# untitled.net
KiCad netlist of a schematic drawn in EAGLE
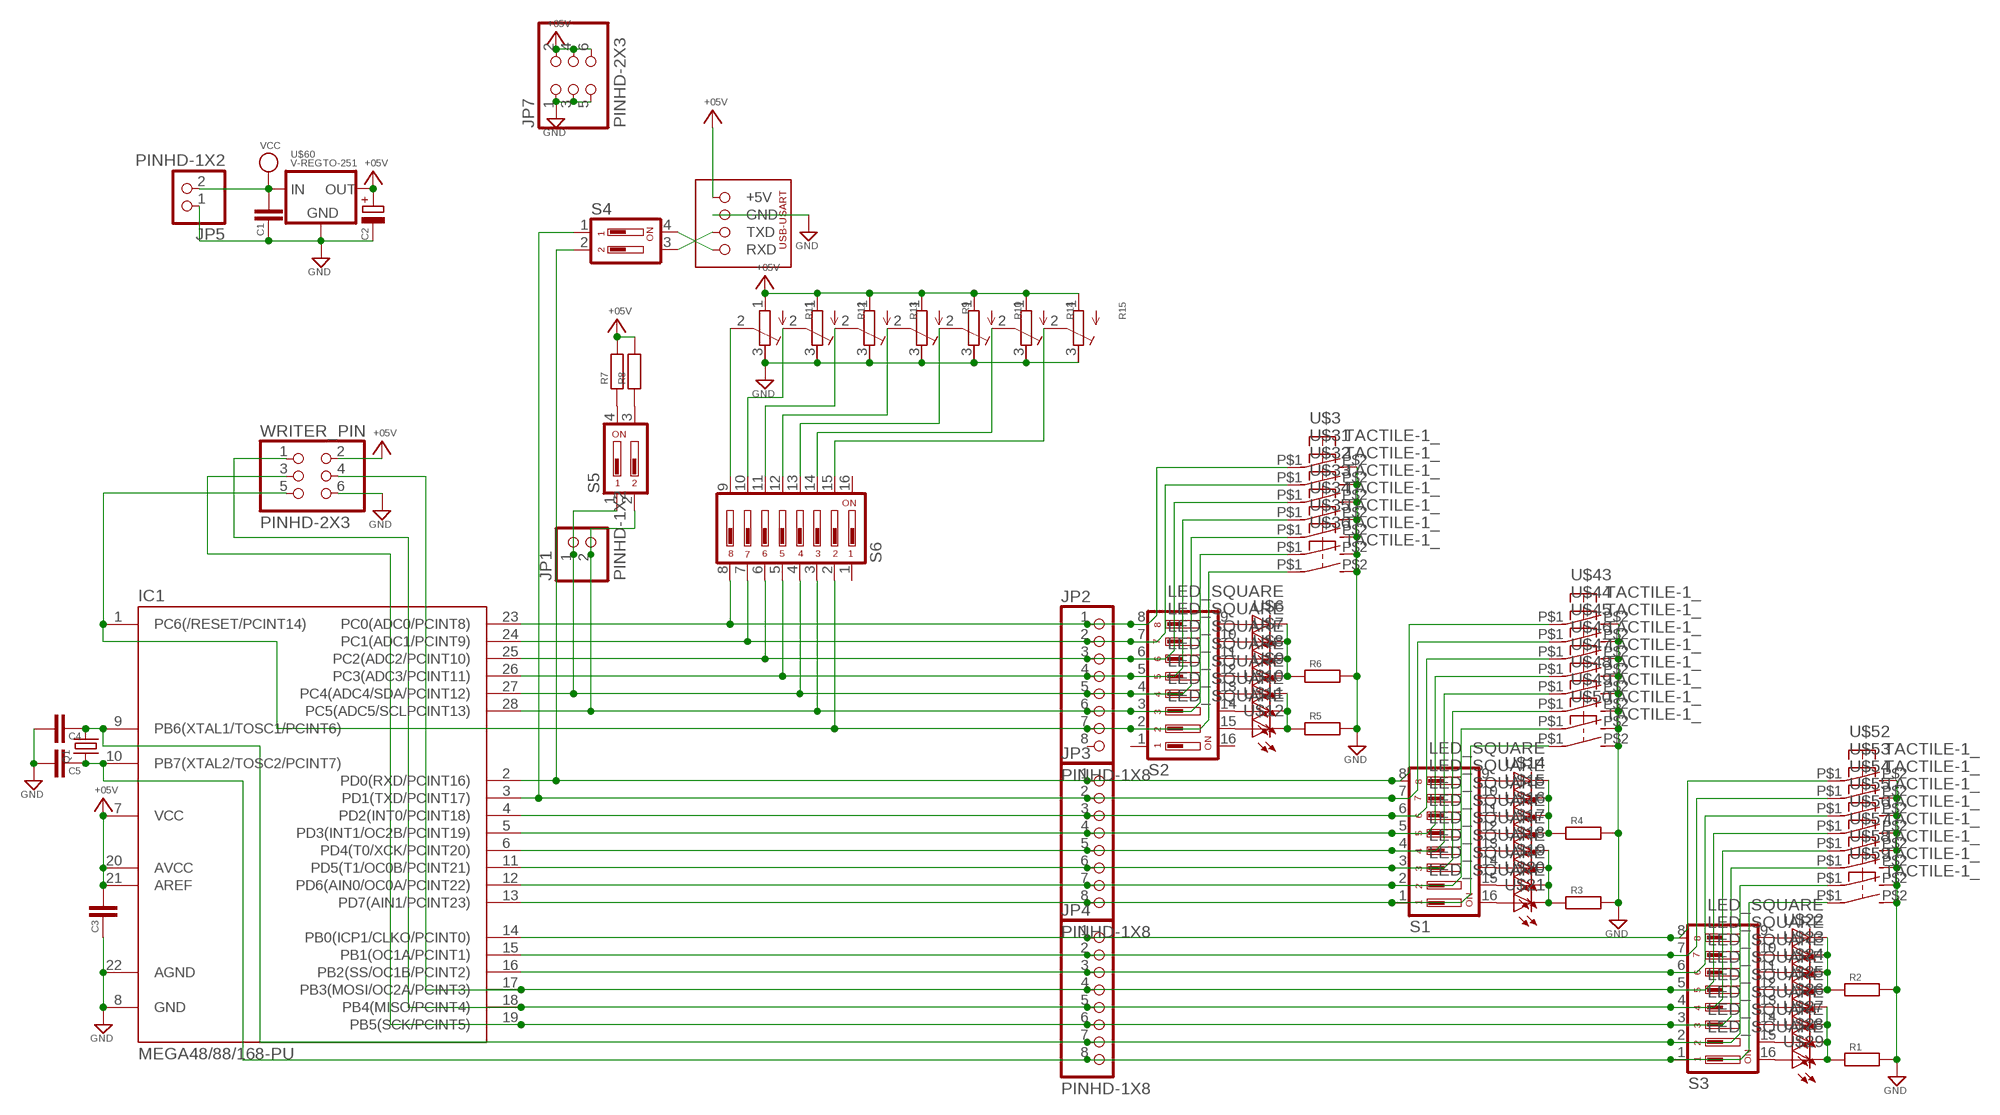
[diagram p0: schematic, sheet 1]

(export (version "E")
  (design (tool "Eeschema 10.0.6"))
  (components
    (comp (ref "C1")
      (value "C-025-025X050")
      (footprint "eagle-import:C025-025X050")
      (libsource (lib "eagle-import") (part "C-025-025X050"))
    )
    (comp (ref "C2")
      (value "CPOL-E2.5-6")
      (footprint "eagle-import:E2,5-6")
      (libsource (lib "eagle-import") (part "CPOL-E2.5-6"))
    )
    (comp (ref "C3")
      (value "C-025-025X050")
      (footprint "eagle-import:C025-025X050")
      (libsource (lib "eagle-import") (part "C-025-025X050"))
    )
    (comp (ref "C4")
      (value "C-025-025X050")
      (footprint "eagle-import:C025-025X050")
      (libsource (lib "eagle-import") (part "C-025-025X050"))
    )
    (comp (ref "C5")
      (value "C-025-025X050")
      (footprint "eagle-import:C025-025X050")
      (libsource (lib "eagle-import") (part "C-025-025X050"))
    )
    (comp (ref "IC1")
      (value "MEGA48/88/168-PU")
      (footprint "eagle-import:DIL28-3")
      (libsource (lib "eagle-import") (part "MEGA48/88/168-PU"))
    )
    (comp (ref "JP1")
      (value "PINHD-1X2")
      (footprint "eagle-import:1X02")
      (libsource (lib "eagle-import") (part "PINHD-1X2"))
    )
    (comp (ref "JP2")
      (value "PINHD-1X8")
      (footprint "eagle-import:1X08")
      (libsource (lib "eagle-import") (part "PINHD-1X8"))
    )
    (comp (ref "JP3")
      (value "PINHD-1X8")
      (footprint "eagle-import:1X08")
      (libsource (lib "eagle-import") (part "PINHD-1X8"))
    )
    (comp (ref "JP4")
      (value "PINHD-1X8")
      (footprint "eagle-import:1X08")
      (libsource (lib "eagle-import") (part "PINHD-1X8"))
    )
    (comp (ref "JP5")
      (value "PINHD-1X2")
      (footprint "eagle-import:1X02")
      (libsource (lib "eagle-import") (part "PINHD-1X2"))
    )
    (comp (ref "JP7")
      (value "PINHD-2X3")
      (footprint "eagle-import:2X03")
      (libsource (lib "eagle-import") (part "PINHD-2X3"))
    )
    (comp (ref "Q1")
      (value "CRYSTALHC49S")
      (footprint "eagle-import:HC49_S")
      (libsource (lib "eagle-import") (part "CRYSTALHC49S"))
    )
    (comp (ref "R1")
      (value "R-EU_1/4W(8MM)")
      (footprint "eagle-import:1_4W(8MM)")
      (libsource (lib "eagle-import") (part "R-EU_1/4W(8MM)"))
    )
    (comp (ref "R2")
      (value "R-EU_1/4W(8MM)")
      (footprint "eagle-import:1_4W(8MM)")
      (libsource (lib "eagle-import") (part "R-EU_1/4W(8MM)"))
    )
    (comp (ref "R3")
      (value "R-EU_1/4W(8MM)")
      (footprint "eagle-import:1_4W(8MM)")
      (libsource (lib "eagle-import") (part "R-EU_1/4W(8MM)"))
    )
    (comp (ref "R4")
      (value "R-EU_1/4W(8MM)")
      (footprint "eagle-import:1_4W(8MM)")
      (libsource (lib "eagle-import") (part "R-EU_1/4W(8MM)"))
    )
    (comp (ref "R5")
      (value "R-EU_1/4W(8MM)")
      (footprint "eagle-import:1_4W(8MM)")
      (libsource (lib "eagle-import") (part "R-EU_1/4W(8MM)"))
    )
    (comp (ref "R6")
      (value "R-EU_1/4W(8MM)")
      (footprint "eagle-import:1_4W(8MM)")
      (libsource (lib "eagle-import") (part "R-EU_1/4W(8MM)"))
    )
    (comp (ref "R7")
      (value "R-EU_1/4W(8MM)")
      (footprint "eagle-import:1_4W(8MM)")
      (libsource (lib "eagle-import") (part "R-EU_1/4W(8MM)"))
    )
    (comp (ref "R8")
      (value "R-EU_1/4W(8MM)")
      (footprint "eagle-import:1_4W(8MM)")
      (libsource (lib "eagle-import") (part "R-EU_1/4W(8MM)"))
    )
    (comp (ref "R9")
      (value "R-TRIMM_3339P")
      (footprint "eagle-import:3339P")
      (libsource (lib "eagle-import") (part "R-TRIMM_3339P"))
    )
    (comp (ref "R10")
      (value "R-TRIMM_3339P")
      (footprint "eagle-import:3339P")
      (libsource (lib "eagle-import") (part "R-TRIMM_3339P"))
    )
    (comp (ref "R11")
      (value "R-TRIMM_3339P")
      (footprint "eagle-import:3339P")
      (libsource (lib "eagle-import") (part "R-TRIMM_3339P"))
    )
    (comp (ref "R12")
      (value "R-TRIMM_3339P")
      (footprint "eagle-import:3339P")
      (libsource (lib "eagle-import") (part "R-TRIMM_3339P"))
    )
    (comp (ref "R13")
      (value "R-TRIMM_3339P")
      (footprint "eagle-import:3339P")
      (libsource (lib "eagle-import") (part "R-TRIMM_3339P"))
    )
    (comp (ref "R14")
      (value "R-TRIMM_3339P")
      (footprint "eagle-import:3339P")
      (libsource (lib "eagle-import") (part "R-TRIMM_3339P"))
    )
    (comp (ref "R15")
      (value "R-TRIMM_3339P")
      (footprint "eagle-import:3339P")
      (libsource (lib "eagle-import") (part "R-TRIMM_3339P"))
    )
    (comp (ref "S1")
      (value "DIP08YL")
      (footprint "eagle-import:DIP08YL")
      (libsource (lib "eagle-import") (part "DIP08YL"))
    )
    (comp (ref "S2")
      (value "DIP08YL")
      (footprint "eagle-import:DIP08YL")
      (libsource (lib "eagle-import") (part "DIP08YL"))
    )
    (comp (ref "S3")
      (value "DIP08YL")
      (footprint "eagle-import:DIP08YL")
      (libsource (lib "eagle-import") (part "DIP08YL"))
    )
    (comp (ref "S4")
      (value "DIP02YL")
      (footprint "eagle-import:DIP02YL")
      (libsource (lib "eagle-import") (part "DIP02YL"))
    )
    (comp (ref "S5")
      (value "DIP02YL")
      (footprint "eagle-import:DIP02YL")
      (libsource (lib "eagle-import") (part "DIP02YL"))
    )
    (comp (ref "S6")
      (value "DIP08YL")
      (footprint "eagle-import:DIP08YL")
      (libsource (lib "eagle-import") (part "DIP08YL"))
    )
    (comp (ref "U$3")
      (value "TACTILE-1_")
      (footprint "eagle-import:TACTILE_")
      (libsource (lib "eagle-import") (part "TACTILE-1_"))
    )
    (comp (ref "U$6")
      (value "LED_SQUARE")
      (footprint "eagle-import:5020")
      (libsource (lib "eagle-import") (part "LED_SQUARE"))
    )
    (comp (ref "U$7")
      (value "LED_SQUARE")
      (footprint "eagle-import:5020")
      (libsource (lib "eagle-import") (part "LED_SQUARE"))
    )
    (comp (ref "U$8")
      (value "LED_SQUARE")
      (footprint "eagle-import:5020")
      (libsource (lib "eagle-import") (part "LED_SQUARE"))
    )
    (comp (ref "U$9")
      (value "LED_SQUARE")
      (footprint "eagle-import:5020")
      (libsource (lib "eagle-import") (part "LED_SQUARE"))
    )
    (comp (ref "U$10")
      (value "LED_SQUARE")
      (footprint "eagle-import:5020")
      (libsource (lib "eagle-import") (part "LED_SQUARE"))
    )
    (comp (ref "U$11")
      (value "LED_SQUARE")
      (footprint "eagle-import:5020")
      (libsource (lib "eagle-import") (part "LED_SQUARE"))
    )
    (comp (ref "U$12")
      (value "LED_SQUARE")
      (footprint "eagle-import:5020")
      (libsource (lib "eagle-import") (part "LED_SQUARE"))
    )
    (comp (ref "U$14")
      (value "LED_SQUARE")
      (footprint "eagle-import:5020")
      (libsource (lib "eagle-import") (part "LED_SQUARE"))
    )
    (comp (ref "U$15")
      (value "LED_SQUARE")
      (footprint "eagle-import:5020")
      (libsource (lib "eagle-import") (part "LED_SQUARE"))
    )
    (comp (ref "U$16")
      (value "LED_SQUARE")
      (footprint "eagle-import:5020")
      (libsource (lib "eagle-import") (part "LED_SQUARE"))
    )
    (comp (ref "U$17")
      (value "LED_SQUARE")
      (footprint "eagle-import:5020")
      (libsource (lib "eagle-import") (part "LED_SQUARE"))
    )
    (comp (ref "U$18")
      (value "LED_SQUARE")
      (footprint "eagle-import:5020")
      (libsource (lib "eagle-import") (part "LED_SQUARE"))
    )
    (comp (ref "U$19")
      (value "LED_SQUARE")
      (footprint "eagle-import:5020")
      (libsource (lib "eagle-import") (part "LED_SQUARE"))
    )
    (comp (ref "U$20")
      (value "LED_SQUARE")
      (footprint "eagle-import:5020")
      (libsource (lib "eagle-import") (part "LED_SQUARE"))
    )
    (comp (ref "U$21")
      (value "LED_SQUARE")
      (footprint "eagle-import:5020")
      (libsource (lib "eagle-import") (part "LED_SQUARE"))
    )
    (comp (ref "U$22")
      (value "LED_SQUARE")
      (footprint "eagle-import:5020")
      (libsource (lib "eagle-import") (part "LED_SQUARE"))
    )
    (comp (ref "U$23")
      (value "LED_SQUARE")
      (footprint "eagle-import:5020")
      (libsource (lib "eagle-import") (part "LED_SQUARE"))
    )
    (comp (ref "U$24")
      (value "LED_SQUARE")
      (footprint "eagle-import:5020")
      (libsource (lib "eagle-import") (part "LED_SQUARE"))
    )
    (comp (ref "U$25")
      (value "LED_SQUARE")
      (footprint "eagle-import:5020")
      (libsource (lib "eagle-import") (part "LED_SQUARE"))
    )
    (comp (ref "U$26")
      (value "LED_SQUARE")
      (footprint "eagle-import:5020")
      (libsource (lib "eagle-import") (part "LED_SQUARE"))
    )
    (comp (ref "U$27")
      (value "LED_SQUARE")
      (footprint "eagle-import:5020")
      (libsource (lib "eagle-import") (part "LED_SQUARE"))
    )
    (comp (ref "U$28")
      (value "LED_SQUARE")
      (footprint "eagle-import:5020")
      (libsource (lib "eagle-import") (part "LED_SQUARE"))
    )
    (comp (ref "U$29")
      (value "LED_SQUARE")
      (footprint "eagle-import:5020")
      (libsource (lib "eagle-import") (part "LED_SQUARE"))
    )
    (comp (ref "U$31")
      (value "TACTILE-1_")
      (footprint "eagle-import:TACTILE_")
      (libsource (lib "eagle-import") (part "TACTILE-1_"))
    )
    (comp (ref "U$32")
      (value "TACTILE-1_")
      (footprint "eagle-import:TACTILE_")
      (libsource (lib "eagle-import") (part "TACTILE-1_"))
    )
    (comp (ref "U$33")
      (value "TACTILE-1_")
      (footprint "eagle-import:TACTILE_")
      (libsource (lib "eagle-import") (part "TACTILE-1_"))
    )
    (comp (ref "U$34")
      (value "TACTILE-1_")
      (footprint "eagle-import:TACTILE_")
      (libsource (lib "eagle-import") (part "TACTILE-1_"))
    )
    (comp (ref "U$35")
      (value "TACTILE-1_")
      (footprint "eagle-import:TACTILE_")
      (libsource (lib "eagle-import") (part "TACTILE-1_"))
    )
    (comp (ref "U$36")
      (value "TACTILE-1_")
      (footprint "eagle-import:TACTILE_")
      (libsource (lib "eagle-import") (part "TACTILE-1_"))
    )
    (comp (ref "U$43")
      (value "TACTILE-1_")
      (footprint "eagle-import:TACTILE_")
      (libsource (lib "eagle-import") (part "TACTILE-1_"))
    )
    (comp (ref "U$44")
      (value "TACTILE-1_")
      (footprint "eagle-import:TACTILE_")
      (libsource (lib "eagle-import") (part "TACTILE-1_"))
    )
    (comp (ref "U$45")
      (value "TACTILE-1_")
      (footprint "eagle-import:TACTILE_")
      (libsource (lib "eagle-import") (part "TACTILE-1_"))
    )
    (comp (ref "U$46")
      (value "TACTILE-1_")
      (footprint "eagle-import:TACTILE_")
      (libsource (lib "eagle-import") (part "TACTILE-1_"))
    )
    (comp (ref "U$47")
      (value "TACTILE-1_")
      (footprint "eagle-import:TACTILE_")
      (libsource (lib "eagle-import") (part "TACTILE-1_"))
    )
    (comp (ref "U$48")
      (value "TACTILE-1_")
      (footprint "eagle-import:TACTILE_")
      (libsource (lib "eagle-import") (part "TACTILE-1_"))
    )
    (comp (ref "U$49")
      (value "TACTILE-1_")
      (footprint "eagle-import:TACTILE_")
      (libsource (lib "eagle-import") (part "TACTILE-1_"))
    )
    (comp (ref "U$50")
      (value "TACTILE-1_")
      (footprint "eagle-import:TACTILE_")
      (libsource (lib "eagle-import") (part "TACTILE-1_"))
    )
    (comp (ref "U$52")
      (value "TACTILE-1_")
      (footprint "eagle-import:TACTILE_")
      (libsource (lib "eagle-import") (part "TACTILE-1_"))
    )
    (comp (ref "U$53")
      (value "TACTILE-1_")
      (footprint "eagle-import:TACTILE_")
      (libsource (lib "eagle-import") (part "TACTILE-1_"))
    )
    (comp (ref "U$54")
      (value "TACTILE-1_")
      (footprint "eagle-import:TACTILE_")
      (libsource (lib "eagle-import") (part "TACTILE-1_"))
    )
    (comp (ref "U$55")
      (value "TACTILE-1_")
      (footprint "eagle-import:TACTILE_")
      (libsource (lib "eagle-import") (part "TACTILE-1_"))
    )
    (comp (ref "U$56")
      (value "TACTILE-1_")
      (footprint "eagle-import:TACTILE_")
      (libsource (lib "eagle-import") (part "TACTILE-1_"))
    )
    (comp (ref "U$57")
      (value "TACTILE-1_")
      (footprint "eagle-import:TACTILE_")
      (libsource (lib "eagle-import") (part "TACTILE-1_"))
    )
    (comp (ref "U$58")
      (value "TACTILE-1_")
      (footprint "eagle-import:TACTILE_")
      (libsource (lib "eagle-import") (part "TACTILE-1_"))
    )
    (comp (ref "U$59")
      (value "TACTILE-1_")
      (footprint "eagle-import:TACTILE_")
      (libsource (lib "eagle-import") (part "TACTILE-1_"))
    )
    (comp (ref "U$60")
      (value "V-REGTO-251")
      (footprint "eagle-import:TO-251")
      (libsource (lib "eagle-import") (part "V-REGTO-251"))
    )
    (comp (ref "U$64")
      (value "AE-FT234X")
      (footprint "eagle-import:AE-FT234X")
      (libsource (lib "eagle-import") (part "AE-FT234X"))
    )
    (comp (ref "WRITER_PIN")
      (value "PINHD-2X3")
      (footprint "eagle-import:2X03")
      (libsource (lib "eagle-import") (part "PINHD-2X3"))
    )
  )
  (nets
    (net (code "1") (name "+05V") (class "Default")
      (node (ref "C2") (pin "+") (pinfunction "+_+") (pintype "passive"))
      (node (ref "C3") (pin "1") (pinfunction "1_1") (pintype "passive"))
      (node (ref "IC1") (pin "20") (pinfunction "AVCC_20") (pintype "passive"))
      (node (ref "IC1") (pin "21") (pinfunction "AREF_21") (pintype "passive"))
      (node (ref "IC1") (pin "7") (pinfunction "VCC_7") (pintype "power_in"))
      (node (ref "JP7") (pin "2") (pinfunction "2_2") (pintype "passive"))
      (node (ref "JP7") (pin "4") (pinfunction "4_4") (pintype "passive"))
      (node (ref "JP7") (pin "6") (pinfunction "6_6") (pintype "passive"))
      (node (ref "R10") (pin "1") (pinfunction "E_1") (pintype "passive"))
      (node (ref "R11") (pin "1") (pinfunction "E_1") (pintype "passive"))
      (node (ref "R12") (pin "1") (pinfunction "E_1") (pintype "passive"))
      (node (ref "R13") (pin "1") (pinfunction "E_1") (pintype "passive"))
      (node (ref "R14") (pin "1") (pinfunction "E_1") (pintype "passive"))
      (node (ref "R15") (pin "1") (pinfunction "E_1") (pintype "passive"))
      (node (ref "R7") (pin "2") (pinfunction "2_2") (pintype "passive"))
      (node (ref "R8") (pin "2") (pinfunction "2_2") (pintype "passive"))
      (node (ref "R9") (pin "1") (pinfunction "E_1") (pintype "passive"))
      (node (ref "U$60") (pin "3") (pinfunction "OUT_3") (pintype "passive"))
      (node (ref "U$64") (pin "P$1") (pinfunction "+5V_P$1") (pintype "bidirectional"))
      (node (ref "WRITER_PIN") (pin "2") (pinfunction "2_2") (pintype "passive"))
    )
    (net (code "2") (name "GND") (class "Default")
      (node (ref "C1") (pin "2") (pinfunction "2_2") (pintype "passive"))
      (node (ref "C2") (pin "-") (pinfunction "-_-") (pintype "passive"))
      (node (ref "C3") (pin "2") (pinfunction "2_2") (pintype "passive"))
      (node (ref "C4") (pin "1") (pinfunction "1_1") (pintype "passive"))
      (node (ref "C5") (pin "1") (pinfunction "1_1") (pintype "passive"))
      (node (ref "IC1") (pin "22") (pinfunction "AGND_22") (pintype "power_in"))
      (node (ref "IC1") (pin "8") (pinfunction "GND_8") (pintype "power_in"))
      (node (ref "JP5") (pin "1") (pinfunction "1_1") (pintype "passive"))
      (node (ref "JP7") (pin "1") (pinfunction "1_1") (pintype "passive"))
      (node (ref "JP7") (pin "3") (pinfunction "3_3") (pintype "passive"))
      (node (ref "JP7") (pin "5") (pinfunction "5_5") (pintype "passive"))
      (node (ref "R1") (pin "2") (pinfunction "2_2") (pintype "passive"))
      (node (ref "R10") (pin "3") (pinfunction "A_3") (pintype "passive"))
      (node (ref "R11") (pin "3") (pinfunction "A_3") (pintype "passive"))
      (node (ref "R12") (pin "3") (pinfunction "A_3") (pintype "passive"))
      (node (ref "R13") (pin "3") (pinfunction "A_3") (pintype "passive"))
      (node (ref "R14") (pin "3") (pinfunction "A_3") (pintype "passive"))
      (node (ref "R15") (pin "3") (pinfunction "A_3") (pintype "passive"))
      (node (ref "R2") (pin "2") (pinfunction "2_2") (pintype "passive"))
      (node (ref "R3") (pin "2") (pinfunction "2_2") (pintype "passive"))
      (node (ref "R4") (pin "2") (pinfunction "2_2") (pintype "passive"))
      (node (ref "R5") (pin "2") (pinfunction "2_2") (pintype "passive"))
      (node (ref "R6") (pin "2") (pinfunction "2_2") (pintype "passive"))
      (node (ref "R9") (pin "3") (pinfunction "A_3") (pintype "passive"))
      (node (ref "U$3") (pin "P$2") (pinfunction "S_P$2") (pintype "passive"))
      (node (ref "U$31") (pin "P$2") (pinfunction "S_P$2") (pintype "passive"))
      (node (ref "U$32") (pin "P$2") (pinfunction "S_P$2") (pintype "passive"))
      (node (ref "U$33") (pin "P$2") (pinfunction "S_P$2") (pintype "passive"))
      (node (ref "U$34") (pin "P$2") (pinfunction "S_P$2") (pintype "passive"))
      (node (ref "U$35") (pin "P$2") (pinfunction "S_P$2") (pintype "passive"))
      (node (ref "U$36") (pin "P$2") (pinfunction "S_P$2") (pintype "passive"))
      (node (ref "U$43") (pin "P$2") (pinfunction "S_P$2") (pintype "passive"))
      (node (ref "U$44") (pin "P$2") (pinfunction "S_P$2") (pintype "passive"))
      (node (ref "U$45") (pin "P$2") (pinfunction "S_P$2") (pintype "passive"))
      (node (ref "U$46") (pin "P$2") (pinfunction "S_P$2") (pintype "passive"))
      (node (ref "U$47") (pin "P$2") (pinfunction "S_P$2") (pintype "passive"))
      (node (ref "U$48") (pin "P$2") (pinfunction "S_P$2") (pintype "passive"))
      (node (ref "U$49") (pin "P$2") (pinfunction "S_P$2") (pintype "passive"))
      (node (ref "U$50") (pin "P$2") (pinfunction "S_P$2") (pintype "passive"))
      (node (ref "U$52") (pin "P$2") (pinfunction "S_P$2") (pintype "passive"))
      (node (ref "U$53") (pin "P$2") (pinfunction "S_P$2") (pintype "passive"))
      (node (ref "U$54") (pin "P$2") (pinfunction "S_P$2") (pintype "passive"))
      (node (ref "U$55") (pin "P$2") (pinfunction "S_P$2") (pintype "passive"))
      (node (ref "U$56") (pin "P$2") (pinfunction "S_P$2") (pintype "passive"))
      (node (ref "U$57") (pin "P$2") (pinfunction "S_P$2") (pintype "passive"))
      (node (ref "U$58") (pin "P$2") (pinfunction "S_P$2") (pintype "passive"))
      (node (ref "U$59") (pin "P$2") (pinfunction "S_P$2") (pintype "passive"))
      (node (ref "U$60") (pin "2") (pinfunction "GND_2") (pintype "input"))
      (node (ref "U$64") (pin "P$2") (pinfunction "GND_P$2") (pintype "bidirectional"))
      (node (ref "WRITER_PIN") (pin "6") (pinfunction "6_6") (pintype "passive"))
    )
    (net (code "3") (name "Net-(IC1-PB0(ICP1{slash}CLKO{slash}PCINT0))") (class "Default")
      (node (ref "IC1") (pin "14") (pinfunction "PB0(ICP1/CLKO/PCINT0)_14") (pintype "bidirectional"))
      (node (ref "JP4") (pin "1") (pinfunction "1_1") (pintype "passive"))
      (node (ref "S3") (pin "8") (pinfunction "8_8") (pintype "passive"))
      (node (ref "U$52") (pin "P$1") (pinfunction "P_P$1") (pintype "passive"))
    )
    (net (code "4") (name "Net-(IC1-PB1(OC1A{slash}PCINT1))") (class "Default")
      (node (ref "IC1") (pin "15") (pinfunction "PB1(OC1A/PCINT1)_15") (pintype "bidirectional"))
      (node (ref "JP4") (pin "2") (pinfunction "2_2") (pintype "passive"))
      (node (ref "S3") (pin "7") (pinfunction "7_7") (pintype "passive"))
      (node (ref "U$53") (pin "P$1") (pinfunction "P_P$1") (pintype "passive"))
    )
    (net (code "5") (name "Net-(IC1-PB2(SS{slash}OC1B{slash}PCINT2))") (class "Default")
      (node (ref "IC1") (pin "16") (pinfunction "PB2(SS/OC1B/PCINT2)_16") (pintype "bidirectional"))
      (node (ref "JP4") (pin "3") (pinfunction "3_3") (pintype "passive"))
      (node (ref "S3") (pin "6") (pinfunction "6_6") (pintype "passive"))
      (node (ref "U$54") (pin "P$1") (pinfunction "P_P$1") (pintype "passive"))
    )
    (net (code "6") (name "Net-(IC1-PB3(MOSI{slash}OC2A{slash}PCINT3))") (class "Default")
      (node (ref "IC1") (pin "17") (pinfunction "PB3(MOSI/OC2A/PCINT3)_17") (pintype "bidirectional"))
      (node (ref "JP4") (pin "4") (pinfunction "4_4") (pintype "passive"))
      (node (ref "S3") (pin "5") (pinfunction "5_5") (pintype "passive"))
      (node (ref "U$55") (pin "P$1") (pinfunction "P_P$1") (pintype "passive"))
      (node (ref "WRITER_PIN") (pin "4") (pinfunction "4_4") (pintype "passive"))
    )
    (net (code "7") (name "Net-(IC1-PB4(MISO{slash}PCINT4))") (class "Default")
      (node (ref "IC1") (pin "18") (pinfunction "PB4(MISO/PCINT4)_18") (pintype "bidirectional"))
      (node (ref "JP4") (pin "5") (pinfunction "5_5") (pintype "passive"))
      (node (ref "S3") (pin "4") (pinfunction "4_4") (pintype "passive"))
      (node (ref "U$56") (pin "P$1") (pinfunction "P_P$1") (pintype "passive"))
      (node (ref "WRITER_PIN") (pin "1") (pinfunction "1_1") (pintype "passive"))
    )
    (net (code "8") (name "Net-(IC1-PB5(SCK{slash}PCINT5))") (class "Default")
      (node (ref "IC1") (pin "19") (pinfunction "PB5(SCK/PCINT5)_19") (pintype "bidirectional"))
      (node (ref "JP4") (pin "6") (pinfunction "6_6") (pintype "passive"))
      (node (ref "S3") (pin "3") (pinfunction "3_3") (pintype "passive"))
      (node (ref "U$57") (pin "P$1") (pinfunction "P_P$1") (pintype "passive"))
      (node (ref "WRITER_PIN") (pin "3") (pinfunction "3_3") (pintype "passive"))
    )
    (net (code "9") (name "Net-(IC1-PB6(XTAL1{slash}TOSC1{slash}PCINT6))") (class "Default")
      (node (ref "C4") (pin "2") (pinfunction "2_2") (pintype "passive"))
      (node (ref "IC1") (pin "9") (pinfunction "PB6(XTAL1/TOSC1/PCINT6)_9") (pintype "bidirectional"))
      (node (ref "JP4") (pin "7") (pinfunction "7_7") (pintype "passive"))
      (node (ref "Q1") (pin "2") (pinfunction "2_2") (pintype "passive"))
      (node (ref "S3") (pin "2") (pinfunction "2_2") (pintype "passive"))
      (node (ref "U$58") (pin "P$1") (pinfunction "P_P$1") (pintype "passive"))
    )
    (net (code "10") (name "Net-(IC1-PB7(XTAL2{slash}TOSC2{slash}PCINT7))") (class "Default")
      (node (ref "C5") (pin "2") (pinfunction "2_2") (pintype "passive"))
      (node (ref "IC1") (pin "10") (pinfunction "PB7(XTAL2/TOSC2/PCINT7)_10") (pintype "bidirectional"))
      (node (ref "JP4") (pin "8") (pinfunction "8_8") (pintype "passive"))
      (node (ref "Q1") (pin "1") (pinfunction "1_1") (pintype "passive"))
      (node (ref "S3") (pin "1") (pinfunction "1_1") (pintype "passive"))
      (node (ref "U$59") (pin "P$1") (pinfunction "P_P$1") (pintype "passive"))
    )
    (net (code "11") (name "Net-(IC1-PC0(ADC0{slash}PCINT8))") (class "Default")
      (node (ref "IC1") (pin "23") (pinfunction "PC0(ADC0/PCINT8)_23") (pintype "bidirectional"))
      (node (ref "JP2") (pin "1") (pinfunction "1_1") (pintype "passive"))
      (node (ref "S2") (pin "8") (pinfunction "8_8") (pintype "passive"))
      (node (ref "S6") (pin "8") (pinfunction "8_8") (pintype "passive"))
      (node (ref "U$3") (pin "P$1") (pinfunction "P_P$1") (pintype "passive"))
    )
    (net (code "12") (name "Net-(IC1-PC1(ADC1{slash}PCINT9))") (class "Default")
      (node (ref "IC1") (pin "24") (pinfunction "PC1(ADC1/PCINT9)_24") (pintype "bidirectional"))
      (node (ref "JP2") (pin "2") (pinfunction "2_2") (pintype "passive"))
      (node (ref "S2") (pin "7") (pinfunction "7_7") (pintype "passive"))
      (node (ref "S6") (pin "7") (pinfunction "7_7") (pintype "passive"))
      (node (ref "U$31") (pin "P$1") (pinfunction "P_P$1") (pintype "passive"))
    )
    (net (code "13") (name "Net-(IC1-PC2(ADC2{slash}PCINT10))") (class "Default")
      (node (ref "IC1") (pin "25") (pinfunction "PC2(ADC2/PCINT10)_25") (pintype "bidirectional"))
      (node (ref "JP2") (pin "3") (pinfunction "3_3") (pintype "passive"))
      (node (ref "S2") (pin "6") (pinfunction "6_6") (pintype "passive"))
      (node (ref "S6") (pin "6") (pinfunction "6_6") (pintype "passive"))
      (node (ref "U$32") (pin "P$1") (pinfunction "P_P$1") (pintype "passive"))
    )
    (net (code "14") (name "Net-(IC1-PC3(ADC3{slash}PCINT11))") (class "Default")
      (node (ref "IC1") (pin "26") (pinfunction "PC3(ADC3/PCINT11)_26") (pintype "bidirectional"))
      (node (ref "JP2") (pin "4") (pinfunction "4_4") (pintype "passive"))
      (node (ref "S2") (pin "5") (pinfunction "5_5") (pintype "passive"))
      (node (ref "S6") (pin "5") (pinfunction "5_5") (pintype "passive"))
      (node (ref "U$33") (pin "P$1") (pinfunction "P_P$1") (pintype "passive"))
    )
    (net (code "15") (name "Net-(IC1-PC4(ADC4{slash}SDA{slash}PCINT12))") (class "Default")
      (node (ref "IC1") (pin "27") (pinfunction "PC4(ADC4/SDA/PCINT12)_27") (pintype "bidirectional"))
      (node (ref "JP1") (pin "1") (pinfunction "1_1") (pintype "passive"))
      (node (ref "JP2") (pin "5") (pinfunction "5_5") (pintype "passive"))
      (node (ref "S2") (pin "4") (pinfunction "4_4") (pintype "passive"))
      (node (ref "S5") (pin "1") (pinfunction "1_1") (pintype "passive"))
      (node (ref "S6") (pin "4") (pinfunction "4_4") (pintype "passive"))
      (node (ref "U$34") (pin "P$1") (pinfunction "P_P$1") (pintype "passive"))
    )
    (net (code "16") (name "Net-(IC1-PC5(ADC5{slash}SCLPCINT13))") (class "Default")
      (node (ref "IC1") (pin "28") (pinfunction "PC5(ADC5/SCLPCINT13)_28") (pintype "bidirectional"))
      (node (ref "JP1") (pin "2") (pinfunction "2_2") (pintype "passive"))
      (node (ref "JP2") (pin "6") (pinfunction "6_6") (pintype "passive"))
      (node (ref "S2") (pin "3") (pinfunction "3_3") (pintype "passive"))
      (node (ref "S5") (pin "2") (pinfunction "2_2") (pintype "passive"))
      (node (ref "S6") (pin "3") (pinfunction "3_3") (pintype "passive"))
      (node (ref "U$35") (pin "P$1") (pinfunction "P_P$1") (pintype "passive"))
    )
    (net (code "17") (name "Net-(IC1-PC6({slash}RESET{slash}PCINT14))") (class "Default")
      (node (ref "IC1") (pin "1") (pinfunction "PC6(/RESET/PCINT14)_1") (pintype "bidirectional"))
      (node (ref "JP2") (pin "7") (pinfunction "7_7") (pintype "passive"))
      (node (ref "S2") (pin "2") (pinfunction "2_2") (pintype "passive"))
      (node (ref "S6") (pin "2") (pinfunction "2_2") (pintype "passive"))
      (node (ref "U$36") (pin "P$1") (pinfunction "P_P$1") (pintype "passive"))
      (node (ref "WRITER_PIN") (pin "5") (pinfunction "5_5") (pintype "passive"))
    )
    (net (code "18") (name "Net-(IC1-PD0(RXD{slash}PCINT16))") (class "Default")
      (node (ref "IC1") (pin "2") (pinfunction "PD0(RXD/PCINT16)_2") (pintype "bidirectional"))
      (node (ref "JP3") (pin "1") (pinfunction "1_1") (pintype "passive"))
      (node (ref "S1") (pin "8") (pinfunction "8_8") (pintype "passive"))
      (node (ref "S4") (pin "2") (pinfunction "2_2") (pintype "passive"))
      (node (ref "U$43") (pin "P$1") (pinfunction "P_P$1") (pintype "passive"))
    )
    (net (code "19") (name "Net-(IC1-PD1(TXD{slash}PCINT17))") (class "Default")
      (node (ref "IC1") (pin "3") (pinfunction "PD1(TXD/PCINT17)_3") (pintype "bidirectional"))
      (node (ref "JP3") (pin "2") (pinfunction "2_2") (pintype "passive"))
      (node (ref "S1") (pin "7") (pinfunction "7_7") (pintype "passive"))
      (node (ref "S4") (pin "1") (pinfunction "1_1") (pintype "passive"))
      (node (ref "U$44") (pin "P$1") (pinfunction "P_P$1") (pintype "passive"))
    )
    (net (code "20") (name "Net-(IC1-PD2(INT0{slash}PCINT18))") (class "Default")
      (node (ref "IC1") (pin "4") (pinfunction "PD2(INT0/PCINT18)_4") (pintype "bidirectional"))
      (node (ref "JP3") (pin "3") (pinfunction "3_3") (pintype "passive"))
      (node (ref "S1") (pin "6") (pinfunction "6_6") (pintype "passive"))
      (node (ref "U$45") (pin "P$1") (pinfunction "P_P$1") (pintype "passive"))
    )
    (net (code "21") (name "Net-(IC1-PD3(INT1{slash}OC2B{slash}PCINT19))") (class "Default")
      (node (ref "IC1") (pin "5") (pinfunction "PD3(INT1/OC2B/PCINT19)_5") (pintype "bidirectional"))
      (node (ref "JP3") (pin "4") (pinfunction "4_4") (pintype "passive"))
      (node (ref "S1") (pin "5") (pinfunction "5_5") (pintype "passive"))
      (node (ref "U$46") (pin "P$1") (pinfunction "P_P$1") (pintype "passive"))
    )
    (net (code "22") (name "Net-(IC1-PD4(T0{slash}XCK{slash}PCINT20))") (class "Default")
      (node (ref "IC1") (pin "6") (pinfunction "PD4(T0/XCK/PCINT20)_6") (pintype "bidirectional"))
      (node (ref "JP3") (pin "5") (pinfunction "5_5") (pintype "passive"))
      (node (ref "S1") (pin "4") (pinfunction "4_4") (pintype "passive"))
      (node (ref "U$47") (pin "P$1") (pinfunction "P_P$1") (pintype "passive"))
    )
    (net (code "23") (name "Net-(IC1-PD5(T1{slash}OC0B{slash}PCINT21))") (class "Default")
      (node (ref "IC1") (pin "11") (pinfunction "PD5(T1/OC0B/PCINT21)_11") (pintype "bidirectional"))
      (node (ref "JP3") (pin "6") (pinfunction "6_6") (pintype "passive"))
      (node (ref "S1") (pin "3") (pinfunction "3_3") (pintype "passive"))
      (node (ref "U$48") (pin "P$1") (pinfunction "P_P$1") (pintype "passive"))
    )
    (net (code "24") (name "Net-(IC1-PD6(AIN0{slash}OC0A{slash}PCINT22))") (class "Default")
      (node (ref "IC1") (pin "12") (pinfunction "PD6(AIN0/OC0A/PCINT22)_12") (pintype "bidirectional"))
      (node (ref "JP3") (pin "7") (pinfunction "7_7") (pintype "passive"))
      (node (ref "S1") (pin "2") (pinfunction "2_2") (pintype "passive"))
      (node (ref "U$49") (pin "P$1") (pinfunction "P_P$1") (pintype "passive"))
    )
    (net (code "25") (name "Net-(IC1-PD7(AIN1{slash}PCINT23))") (class "Default")
      (node (ref "IC1") (pin "13") (pinfunction "PD7(AIN1/PCINT23)_13") (pintype "bidirectional"))
      (node (ref "JP3") (pin "8") (pinfunction "8_8") (pintype "passive"))
      (node (ref "S1") (pin "1") (pinfunction "1_1") (pintype "passive"))
      (node (ref "U$50") (pin "P$1") (pinfunction "P_P$1") (pintype "passive"))
    )
    (net (code "26") (name "Net-(R7-Pad1)") (class "Default")
      (node (ref "R7") (pin "1") (pinfunction "1_1") (pintype "passive"))
      (node (ref "S5") (pin "4") (pinfunction "4_4") (pintype "passive"))
    )
    (net (code "27") (name "Net-(R8-Pad1)") (class "Default")
      (node (ref "R8") (pin "1") (pinfunction "1_1") (pintype "passive"))
      (node (ref "S5") (pin "3") (pinfunction "3_3") (pintype "passive"))
    )
    (net (code "28") (name "Net-(R9-S)") (class "Default")
      (node (ref "R9") (pin "2") (pinfunction "S_2") (pintype "passive"))
      (node (ref "S6") (pin "12") (pinfunction "12_12") (pintype "passive"))
    )
    (net (code "29") (name "Net-(R10-S)") (class "Default")
      (node (ref "R10") (pin "2") (pinfunction "S_2") (pintype "passive"))
      (node (ref "S6") (pin "13") (pinfunction "13_13") (pintype "passive"))
    )
    (net (code "30") (name "Net-(R11-S)") (class "Default")
      (node (ref "R11") (pin "2") (pinfunction "S_2") (pintype "passive"))
      (node (ref "S6") (pin "9") (pinfunction "9_9") (pintype "passive"))
    )
    (net (code "31") (name "Net-(R12-S)") (class "Default")
      (node (ref "R12") (pin "2") (pinfunction "S_2") (pintype "passive"))
      (node (ref "S6") (pin "10") (pinfunction "10_10") (pintype "passive"))
    )
    (net (code "32") (name "Net-(R13-S)") (class "Default")
      (node (ref "R13") (pin "2") (pinfunction "S_2") (pintype "passive"))
      (node (ref "S6") (pin "11") (pinfunction "11_11") (pintype "passive"))
    )
    (net (code "33") (name "Net-(R14-S)") (class "Default")
      (node (ref "R14") (pin "2") (pinfunction "S_2") (pintype "passive"))
      (node (ref "S6") (pin "14") (pinfunction "14_14") (pintype "passive"))
    )
    (net (code "34") (name "Net-(R15-S)") (class "Default")
      (node (ref "R15") (pin "2") (pinfunction "S_2") (pintype "passive"))
      (node (ref "S6") (pin "15") (pinfunction "15_15") (pintype "passive"))
    )
    (net (code "35") (name "Net-(U$6-A)") (class "Default")
      (node (ref "S2") (pin "9") (pinfunction "9_9") (pintype "passive"))
      (node (ref "U$6") (pin "P$1") (pinfunction "A_P$1") (pintype "passive"))
    )
    (net (code "36") (name "Net-(U$6-C)") (class "Default")
      (node (ref "R6") (pin "1") (pinfunction "1_1") (pintype "passive"))
      (node (ref "U$6") (pin "P$2") (pinfunction "C_P$2") (pintype "passive"))
      (node (ref "U$7") (pin "P$2") (pinfunction "C_P$2") (pintype "passive"))
      (node (ref "U$8") (pin "P$2") (pinfunction "C_P$2") (pintype "passive"))
      (node (ref "U$9") (pin "P$2") (pinfunction "C_P$2") (pintype "passive"))
    )
    (net (code "37") (name "Net-(U$7-A)") (class "Default")
      (node (ref "S2") (pin "10") (pinfunction "10_10") (pintype "passive"))
      (node (ref "U$7") (pin "P$1") (pinfunction "A_P$1") (pintype "passive"))
    )
    (net (code "38") (name "Net-(U$8-A)") (class "Default")
      (node (ref "S2") (pin "11") (pinfunction "11_11") (pintype "passive"))
      (node (ref "U$8") (pin "P$1") (pinfunction "A_P$1") (pintype "passive"))
    )
    (net (code "39") (name "Net-(U$9-A)") (class "Default")
      (node (ref "S2") (pin "12") (pinfunction "12_12") (pintype "passive"))
      (node (ref "U$9") (pin "P$1") (pinfunction "A_P$1") (pintype "passive"))
    )
    (net (code "40") (name "Net-(U$10-A)") (class "Default")
      (node (ref "S2") (pin "13") (pinfunction "13_13") (pintype "passive"))
      (node (ref "U$10") (pin "P$1") (pinfunction "A_P$1") (pintype "passive"))
    )
    (net (code "41") (name "Net-(U$10-C)") (class "Default")
      (node (ref "R5") (pin "1") (pinfunction "1_1") (pintype "passive"))
      (node (ref "U$10") (pin "P$2") (pinfunction "C_P$2") (pintype "passive"))
      (node (ref "U$11") (pin "P$2") (pinfunction "C_P$2") (pintype "passive"))
      (node (ref "U$12") (pin "P$2") (pinfunction "C_P$2") (pintype "passive"))
    )
    (net (code "42") (name "Net-(U$11-A)") (class "Default")
      (node (ref "S2") (pin "14") (pinfunction "14_14") (pintype "passive"))
      (node (ref "U$11") (pin "P$1") (pinfunction "A_P$1") (pintype "passive"))
    )
    (net (code "43") (name "Net-(U$12-A)") (class "Default")
      (node (ref "S2") (pin "15") (pinfunction "15_15") (pintype "passive"))
      (node (ref "U$12") (pin "P$1") (pinfunction "A_P$1") (pintype "passive"))
    )
    (net (code "44") (name "Net-(U$14-A)") (class "Default")
      (node (ref "S1") (pin "9") (pinfunction "9_9") (pintype "passive"))
      (node (ref "U$14") (pin "P$1") (pinfunction "A_P$1") (pintype "passive"))
    )
    (net (code "45") (name "Net-(U$14-C)") (class "Default")
      (node (ref "R4") (pin "1") (pinfunction "1_1") (pintype "passive"))
      (node (ref "U$14") (pin "P$2") (pinfunction "C_P$2") (pintype "passive"))
      (node (ref "U$15") (pin "P$2") (pinfunction "C_P$2") (pintype "passive"))
      (node (ref "U$16") (pin "P$2") (pinfunction "C_P$2") (pintype "passive"))
      (node (ref "U$17") (pin "P$2") (pinfunction "C_P$2") (pintype "passive"))
    )
    (net (code "46") (name "Net-(U$15-A)") (class "Default")
      (node (ref "S1") (pin "10") (pinfunction "10_10") (pintype "passive"))
      (node (ref "U$15") (pin "P$1") (pinfunction "A_P$1") (pintype "passive"))
    )
    (net (code "47") (name "Net-(U$16-A)") (class "Default")
      (node (ref "S1") (pin "11") (pinfunction "11_11") (pintype "passive"))
      (node (ref "U$16") (pin "P$1") (pinfunction "A_P$1") (pintype "passive"))
    )
    (net (code "48") (name "Net-(U$17-A)") (class "Default")
      (node (ref "S1") (pin "12") (pinfunction "12_12") (pintype "passive"))
      (node (ref "U$17") (pin "P$1") (pinfunction "A_P$1") (pintype "passive"))
    )
    (net (code "49") (name "Net-(U$18-A)") (class "Default")
      (node (ref "S1") (pin "13") (pinfunction "13_13") (pintype "passive"))
      (node (ref "U$18") (pin "P$1") (pinfunction "A_P$1") (pintype "passive"))
    )
    (net (code "50") (name "Net-(U$18-C)") (class "Default")
      (node (ref "R3") (pin "1") (pinfunction "1_1") (pintype "passive"))
      (node (ref "U$18") (pin "P$2") (pinfunction "C_P$2") (pintype "passive"))
      (node (ref "U$19") (pin "P$2") (pinfunction "C_P$2") (pintype "passive"))
      (node (ref "U$20") (pin "P$2") (pinfunction "C_P$2") (pintype "passive"))
      (node (ref "U$21") (pin "P$2") (pinfunction "C_P$2") (pintype "passive"))
    )
    (net (code "51") (name "Net-(U$19-A)") (class "Default")
      (node (ref "S1") (pin "14") (pinfunction "14_14") (pintype "passive"))
      (node (ref "U$19") (pin "P$1") (pinfunction "A_P$1") (pintype "passive"))
    )
    (net (code "52") (name "Net-(U$20-A)") (class "Default")
      (node (ref "S1") (pin "15") (pinfunction "15_15") (pintype "passive"))
      (node (ref "U$20") (pin "P$1") (pinfunction "A_P$1") (pintype "passive"))
    )
    (net (code "53") (name "Net-(U$21-A)") (class "Default")
      (node (ref "S1") (pin "16") (pinfunction "16_16") (pintype "passive"))
      (node (ref "U$21") (pin "P$1") (pinfunction "A_P$1") (pintype "passive"))
    )
    (net (code "54") (name "Net-(U$22-A)") (class "Default")
      (node (ref "S3") (pin "9") (pinfunction "9_9") (pintype "passive"))
      (node (ref "U$22") (pin "P$1") (pinfunction "A_P$1") (pintype "passive"))
    )
    (net (code "55") (name "Net-(U$22-C)") (class "Default")
      (node (ref "R2") (pin "1") (pinfunction "1_1") (pintype "passive"))
      (node (ref "U$22") (pin "P$2") (pinfunction "C_P$2") (pintype "passive"))
      (node (ref "U$23") (pin "P$2") (pinfunction "C_P$2") (pintype "passive"))
      (node (ref "U$24") (pin "P$2") (pinfunction "C_P$2") (pintype "passive"))
      (node (ref "U$25") (pin "P$2") (pinfunction "C_P$2") (pintype "passive"))
    )
    (net (code "56") (name "Net-(U$23-A)") (class "Default")
      (node (ref "S3") (pin "10") (pinfunction "10_10") (pintype "passive"))
      (node (ref "U$23") (pin "P$1") (pinfunction "A_P$1") (pintype "passive"))
    )
    (net (code "57") (name "Net-(U$24-A)") (class "Default")
      (node (ref "S3") (pin "11") (pinfunction "11_11") (pintype "passive"))
      (node (ref "U$24") (pin "P$1") (pinfunction "A_P$1") (pintype "passive"))
    )
    (net (code "58") (name "Net-(U$25-A)") (class "Default")
      (node (ref "S3") (pin "12") (pinfunction "12_12") (pintype "passive"))
      (node (ref "U$25") (pin "P$1") (pinfunction "A_P$1") (pintype "passive"))
    )
    (net (code "59") (name "Net-(U$26-A)") (class "Default")
      (node (ref "S3") (pin "13") (pinfunction "13_13") (pintype "passive"))
      (node (ref "U$26") (pin "P$1") (pinfunction "A_P$1") (pintype "passive"))
    )
    (net (code "60") (name "Net-(U$26-C)") (class "Default")
      (node (ref "R1") (pin "1") (pinfunction "1_1") (pintype "passive"))
      (node (ref "U$26") (pin "P$2") (pinfunction "C_P$2") (pintype "passive"))
      (node (ref "U$27") (pin "P$2") (pinfunction "C_P$2") (pintype "passive"))
      (node (ref "U$28") (pin "P$2") (pinfunction "C_P$2") (pintype "passive"))
      (node (ref "U$29") (pin "P$2") (pinfunction "C_P$2") (pintype "passive"))
    )
    (net (code "61") (name "Net-(U$27-A)") (class "Default")
      (node (ref "S3") (pin "14") (pinfunction "14_14") (pintype "passive"))
      (node (ref "U$27") (pin "P$1") (pinfunction "A_P$1") (pintype "passive"))
    )
    (net (code "62") (name "Net-(U$28-A)") (class "Default")
      (node (ref "S3") (pin "15") (pinfunction "15_15") (pintype "passive"))
      (node (ref "U$28") (pin "P$1") (pinfunction "A_P$1") (pintype "passive"))
    )
    (net (code "63") (name "Net-(U$29-A)") (class "Default")
      (node (ref "S3") (pin "16") (pinfunction "16_16") (pintype "passive"))
      (node (ref "U$29") (pin "P$1") (pinfunction "A_P$1") (pintype "passive"))
    )
    (net (code "64") (name "Net-(U$64-RXD)") (class "Default")
      (node (ref "S4") (pin "4") (pinfunction "4_4") (pintype "passive"))
      (node (ref "U$64") (pin "P$4") (pinfunction "RXD_P$4") (pintype "bidirectional"))
    )
    (net (code "65") (name "Net-(U$64-TXD)") (class "Default")
      (node (ref "S4") (pin "3") (pinfunction "3_3") (pintype "passive"))
      (node (ref "U$64") (pin "P$3") (pinfunction "TXD_P$3") (pintype "bidirectional"))
    )
    (net (code "66") (name "VCC") (class "Default")
      (node (ref "C1") (pin "1") (pinfunction "1_1") (pintype "passive"))
      (node (ref "JP5") (pin "2") (pinfunction "2_2") (pintype "passive"))
      (node (ref "U$60") (pin "1") (pinfunction "IN_1") (pintype "input"))
    )
    (net (code "67") (name "unconnected-(JP2-Pad8)") (class "Default")
      (node (ref "JP2") (pin "8") (pinfunction "8_8") (pintype "passive"))
    )
    (net (code "68") (name "unconnected-(S2-Pad1)") (class "Default")
      (node (ref "S2") (pin "1") (pinfunction "1_1") (pintype "passive"))
    )
    (net (code "69") (name "unconnected-(S2-Pad16)") (class "Default")
      (node (ref "S2") (pin "16") (pinfunction "16_16") (pintype "passive"))
    )
    (net (code "70") (name "unconnected-(S6-Pad1)") (class "Default")
      (node (ref "S6") (pin "1") (pinfunction "1_1") (pintype "passive"))
    )
    (net (code "71") (name "unconnected-(S6-Pad16)") (class "Default")
      (node (ref "S6") (pin "16") (pinfunction "16_16") (pintype "passive"))
    )
  )
)
